# AdcPmodDigital.net
KiCad netlist of a schematic drawn in Altium Designer
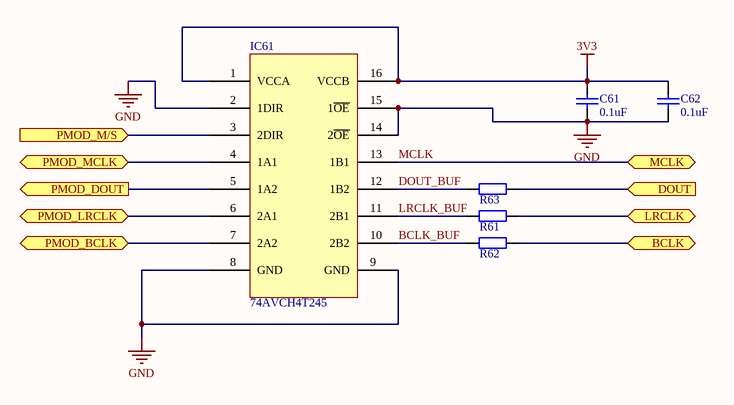
[diagram p0: AdcPmodDigital.SchDoc]

(export (version "E")
  (design (tool "Eeschema 10.0.6"))
  (components
    (comp (ref "C61")
      (value "0.1uF")
      (footprint "CAP0805")
      (description "Ceramic X7R")
      (fields (field (name "MANUFACTURER") "AVX") (field (name "MFR. PART NO.") "08055C104KAT2A"))
      (libsource (lib "AdcPmod") (part "CAP"))
    )
    (comp (ref "C62")
      (value "0.1uF")
      (footprint "CAP0805")
      (description "Ceramic X7R")
      (fields (field (name "MANUFACTURER") "AVX") (field (name "MFR. PART NO.") "08055C104KAT2A"))
      (libsource (lib "AdcPmod") (part "CAP"))
    )
    (comp (ref "IC61")
      (value "74AVCH4T245")
      (footprint "TSSOP16")
      (description "Translation - Voltage Levels 4-Bit Dual-Supply Bus Xcvr")
      (fields
        (field (name "MANUFACTURER") "Texas Instruments")
        (field (name "MFR. PART NO.") "SN74AVCH4T245PWR")
      )
      (libsource (lib "AdcPmod") (part "74AVCH4T245"))
    )
    (comp (ref "R61")
      (value "RES")
      (footprint "RES0805")
      (description "Resistor")
      (libsource (lib "AdcPmod") (part "RES"))
    )
    (comp (ref "R62")
      (value "RES")
      (footprint "RES0805")
      (description "Resistor")
      (libsource (lib "AdcPmod") (part "RES"))
    )
    (comp (ref "R63")
      (value "RES")
      (footprint "RES0805")
      (description "Resistor")
      (libsource (lib "AdcPmod") (part "RES"))
    )
  )
  (nets
    (net (code "1") (name "/BCLK") (class "Default")
      (node (ref "R62") (pin "2") (pinfunction "2_2") (pintype "passive"))
    )
    (net (code "2") (name "/BCLK_BUF") (class "Default")
      (node (ref "IC61") (pin "10") (pinfunction "2B2_10") (pintype "passive"))
      (node (ref "R62") (pin "1") (pinfunction "1_1") (pintype "passive"))
    )
    (net (code "3") (name "/DOUT") (class "Default")
      (node (ref "R63") (pin "2") (pinfunction "2_2") (pintype "passive"))
    )
    (net (code "4") (name "/DOUT_BUF") (class "Default")
      (node (ref "IC61") (pin "12") (pinfunction "1B2_12") (pintype "passive"))
      (node (ref "R63") (pin "1") (pinfunction "1_1") (pintype "passive"))
    )
    (net (code "5") (name "/LRCLK") (class "Default")
      (node (ref "R61") (pin "2") (pinfunction "2_2") (pintype "passive"))
    )
    (net (code "6") (name "/LRCLK_BUF") (class "Default")
      (node (ref "IC61") (pin "11") (pinfunction "2B1_11") (pintype "passive"))
      (node (ref "R61") (pin "1") (pinfunction "1_1") (pintype "passive"))
    )
    (net (code "7") (name "/MCLK") (class "Default")
      (node (ref "IC61") (pin "13") (pinfunction "1B1_13") (pintype "passive"))
    )
    (net (code "8") (name "/PMOD_BCLK") (class "Default")
      (node (ref "IC61") (pin "7") (pinfunction "2A2_7") (pintype "passive"))
    )
    (net (code "9") (name "/PMOD_DOUT") (class "Default")
      (node (ref "IC61") (pin "5") (pinfunction "1A2_5") (pintype "passive"))
    )
    (net (code "10") (name "/PMOD_LRCLK") (class "Default")
      (node (ref "IC61") (pin "6") (pinfunction "2A1_6") (pintype "passive"))
    )
    (net (code "11") (name "/PMOD_MCLK") (class "Default")
      (node (ref "IC61") (pin "4") (pinfunction "1A1_4") (pintype "passive"))
    )
    (net (code "12") (name "/PMOD_M{slash}S") (class "Default")
      (node (ref "IC61") (pin "3") (pinfunction "2DIR_3") (pintype "passive"))
    )
    (net (code "13") (name "3V3") (class "Default")
      (node (ref "C61") (pin "2") (pinfunction "2_2") (pintype "passive"))
      (node (ref "C62") (pin "2") (pinfunction "2_2") (pintype "passive"))
      (node (ref "IC61") (pin "1") (pinfunction "VCCA_1") (pintype "passive"))
      (node (ref "IC61") (pin "16") (pinfunction "VCCB_16") (pintype "passive"))
    )
    (net (code "14") (name "GND") (class "Default")
      (node (ref "C61") (pin "1") (pinfunction "1_1") (pintype "passive"))
      (node (ref "C62") (pin "1") (pinfunction "1_1") (pintype "passive"))
      (node (ref "IC61") (pin "14") (pinfunction "2~{OE}_14") (pintype "passive"))
      (node (ref "IC61") (pin "15") (pinfunction "1~{OE}_15") (pintype "passive"))
      (node (ref "IC61") (pin "2") (pinfunction "1DIR_2") (pintype "passive"))
      (node (ref "IC61") (pin "8") (pinfunction "GND_8") (pintype "passive"))
      (node (ref "IC61") (pin "9") (pinfunction "GND_9") (pintype "passive"))
    )
  )
)
